# Monitor_strip.net
KiCad netlist of a schematic drawn in EAGLE
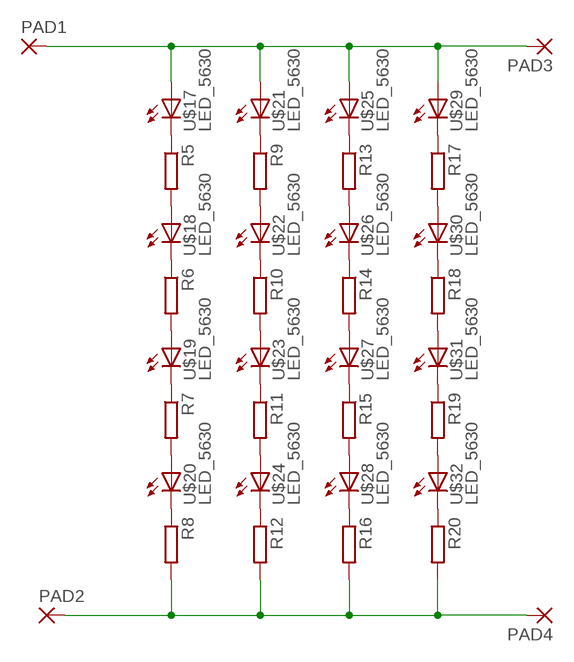
[diagram p0: schematic, sheet 1]

(export (version "E")
  (design (tool "Eeschema 10.0.6"))
  (components
    (comp (ref "PAD1")
      (value "SMD2")
      (footprint "eagle-import:SMD1,27-2,54")
      (libsource (lib "eagle-import") (part "SMD2"))
    )
    (comp (ref "PAD2")
      (value "SMD2")
      (footprint "eagle-import:SMD1,27-2,54")
      (libsource (lib "eagle-import") (part "SMD2"))
    )
    (comp (ref "PAD3")
      (value "SMD2")
      (footprint "eagle-import:SMD1,27-2,54")
      (libsource (lib "eagle-import") (part "SMD2"))
    )
    (comp (ref "PAD4")
      (value "SMD2")
      (footprint "eagle-import:SMD1,27-2,54")
      (libsource (lib "eagle-import") (part "SMD2"))
    )
    (comp (ref "R5")
      (value "R_0805")
      (footprint "eagle-import:R0805")
      (libsource (lib "eagle-import") (part "R_0805"))
    )
    (comp (ref "R6")
      (value "R_0805")
      (footprint "eagle-import:R0805")
      (libsource (lib "eagle-import") (part "R_0805"))
    )
    (comp (ref "R7")
      (value "R_0805")
      (footprint "eagle-import:R0805")
      (libsource (lib "eagle-import") (part "R_0805"))
    )
    (comp (ref "R8")
      (value "R_0805")
      (footprint "eagle-import:R0805")
      (libsource (lib "eagle-import") (part "R_0805"))
    )
    (comp (ref "R9")
      (value "R_0805")
      (footprint "eagle-import:R0805")
      (libsource (lib "eagle-import") (part "R_0805"))
    )
    (comp (ref "R10")
      (value "R_0805")
      (footprint "eagle-import:R0805")
      (libsource (lib "eagle-import") (part "R_0805"))
    )
    (comp (ref "R11")
      (value "R_0805")
      (footprint "eagle-import:R0805")
      (libsource (lib "eagle-import") (part "R_0805"))
    )
    (comp (ref "R12")
      (value "R_0805")
      (footprint "eagle-import:R0805")
      (libsource (lib "eagle-import") (part "R_0805"))
    )
    (comp (ref "R13")
      (value "R_0805")
      (footprint "eagle-import:R0805")
      (libsource (lib "eagle-import") (part "R_0805"))
    )
    (comp (ref "R14")
      (value "R_0805")
      (footprint "eagle-import:R0805")
      (libsource (lib "eagle-import") (part "R_0805"))
    )
    (comp (ref "R15")
      (value "R_0805")
      (footprint "eagle-import:R0805")
      (libsource (lib "eagle-import") (part "R_0805"))
    )
    (comp (ref "R16")
      (value "R_0805")
      (footprint "eagle-import:R0805")
      (libsource (lib "eagle-import") (part "R_0805"))
    )
    (comp (ref "R17")
      (value "R_0805")
      (footprint "eagle-import:R0805")
      (libsource (lib "eagle-import") (part "R_0805"))
    )
    (comp (ref "R18")
      (value "R_0805")
      (footprint "eagle-import:R0805")
      (libsource (lib "eagle-import") (part "R_0805"))
    )
    (comp (ref "R19")
      (value "R_0805")
      (footprint "eagle-import:R0805")
      (libsource (lib "eagle-import") (part "R_0805"))
    )
    (comp (ref "R20")
      (value "R_0805")
      (footprint "eagle-import:R0805")
      (libsource (lib "eagle-import") (part "R_0805"))
    )
    (comp (ref "U$17")
      (value "LED_5630")
      (footprint "eagle-import:LED5730")
      (libsource (lib "eagle-import") (part "LED_5630"))
    )
    (comp (ref "U$18")
      (value "LED_5630")
      (footprint "eagle-import:LED5730")
      (libsource (lib "eagle-import") (part "LED_5630"))
    )
    (comp (ref "U$19")
      (value "LED_5630")
      (footprint "eagle-import:LED5730")
      (libsource (lib "eagle-import") (part "LED_5630"))
    )
    (comp (ref "U$20")
      (value "LED_5630")
      (footprint "eagle-import:LED5730")
      (libsource (lib "eagle-import") (part "LED_5630"))
    )
    (comp (ref "U$21")
      (value "LED_5630")
      (footprint "eagle-import:LED5730")
      (libsource (lib "eagle-import") (part "LED_5630"))
    )
    (comp (ref "U$22")
      (value "LED_5630")
      (footprint "eagle-import:LED5730")
      (libsource (lib "eagle-import") (part "LED_5630"))
    )
    (comp (ref "U$23")
      (value "LED_5630")
      (footprint "eagle-import:LED5730")
      (libsource (lib "eagle-import") (part "LED_5630"))
    )
    (comp (ref "U$24")
      (value "LED_5630")
      (footprint "eagle-import:LED5730")
      (libsource (lib "eagle-import") (part "LED_5630"))
    )
    (comp (ref "U$25")
      (value "LED_5630")
      (footprint "eagle-import:LED5730")
      (libsource (lib "eagle-import") (part "LED_5630"))
    )
    (comp (ref "U$26")
      (value "LED_5630")
      (footprint "eagle-import:LED5730")
      (libsource (lib "eagle-import") (part "LED_5630"))
    )
    (comp (ref "U$27")
      (value "LED_5630")
      (footprint "eagle-import:LED5730")
      (libsource (lib "eagle-import") (part "LED_5630"))
    )
    (comp (ref "U$28")
      (value "LED_5630")
      (footprint "eagle-import:LED5730")
      (libsource (lib "eagle-import") (part "LED_5630"))
    )
    (comp (ref "U$29")
      (value "LED_5630")
      (footprint "eagle-import:LED5730")
      (libsource (lib "eagle-import") (part "LED_5630"))
    )
    (comp (ref "U$30")
      (value "LED_5630")
      (footprint "eagle-import:LED5730")
      (libsource (lib "eagle-import") (part "LED_5630"))
    )
    (comp (ref "U$31")
      (value "LED_5630")
      (footprint "eagle-import:LED5730")
      (libsource (lib "eagle-import") (part "LED_5630"))
    )
    (comp (ref "U$32")
      (value "LED_5630")
      (footprint "eagle-import:LED5730")
      (libsource (lib "eagle-import") (part "LED_5630"))
    )
  )
  (nets
    (net (code "1") (name "Net-(PAD1-P)") (class "Default")
      (node (ref "PAD1") (pin "1") (pinfunction "P_1") (pintype "passive"))
      (node (ref "PAD3") (pin "1") (pinfunction "P_1") (pintype "passive"))
      (node (ref "U$17") (pin "A") (pinfunction "A_A") (pintype "passive"))
      (node (ref "U$17") (pin "A1") (pinfunction "A_A1") (pintype "passive"))
      (node (ref "U$21") (pin "A") (pinfunction "A_A") (pintype "passive"))
      (node (ref "U$21") (pin "A1") (pinfunction "A_A1") (pintype "passive"))
      (node (ref "U$25") (pin "A") (pinfunction "A_A") (pintype "passive"))
      (node (ref "U$25") (pin "A1") (pinfunction "A_A1") (pintype "passive"))
      (node (ref "U$29") (pin "A") (pinfunction "A_A") (pintype "passive"))
      (node (ref "U$29") (pin "A1") (pinfunction "A_A1") (pintype "passive"))
    )
    (net (code "2") (name "Net-(PAD2-P)") (class "Default")
      (node (ref "PAD2") (pin "1") (pinfunction "P_1") (pintype "passive"))
      (node (ref "PAD4") (pin "1") (pinfunction "P_1") (pintype "passive"))
      (node (ref "R12") (pin "2") (pinfunction "2_2") (pintype "passive"))
      (node (ref "R16") (pin "2") (pinfunction "2_2") (pintype "passive"))
      (node (ref "R20") (pin "2") (pinfunction "2_2") (pintype "passive"))
      (node (ref "R8") (pin "2") (pinfunction "2_2") (pintype "passive"))
    )
    (net (code "3") (name "Net-(R5-Pad1)") (class "Default")
      (node (ref "R5") (pin "1") (pinfunction "1_1") (pintype "passive"))
      (node (ref "U$17") (pin "C") (pinfunction "C_C") (pintype "passive"))
    )
    (net (code "4") (name "Net-(R5-Pad2)") (class "Default")
      (node (ref "R5") (pin "2") (pinfunction "2_2") (pintype "passive"))
      (node (ref "U$18") (pin "A") (pinfunction "A_A") (pintype "passive"))
      (node (ref "U$18") (pin "A1") (pinfunction "A_A1") (pintype "passive"))
    )
    (net (code "5") (name "Net-(R6-Pad1)") (class "Default")
      (node (ref "R6") (pin "1") (pinfunction "1_1") (pintype "passive"))
      (node (ref "U$18") (pin "C") (pinfunction "C_C") (pintype "passive"))
    )
    (net (code "6") (name "Net-(R6-Pad2)") (class "Default")
      (node (ref "R6") (pin "2") (pinfunction "2_2") (pintype "passive"))
      (node (ref "U$19") (pin "A") (pinfunction "A_A") (pintype "passive"))
      (node (ref "U$19") (pin "A1") (pinfunction "A_A1") (pintype "passive"))
    )
    (net (code "7") (name "Net-(R7-Pad1)") (class "Default")
      (node (ref "R7") (pin "1") (pinfunction "1_1") (pintype "passive"))
      (node (ref "U$19") (pin "C") (pinfunction "C_C") (pintype "passive"))
    )
    (net (code "8") (name "Net-(R7-Pad2)") (class "Default")
      (node (ref "R7") (pin "2") (pinfunction "2_2") (pintype "passive"))
      (node (ref "U$20") (pin "A") (pinfunction "A_A") (pintype "passive"))
      (node (ref "U$20") (pin "A1") (pinfunction "A_A1") (pintype "passive"))
    )
    (net (code "9") (name "Net-(R8-Pad1)") (class "Default")
      (node (ref "R8") (pin "1") (pinfunction "1_1") (pintype "passive"))
      (node (ref "U$20") (pin "C") (pinfunction "C_C") (pintype "passive"))
    )
    (net (code "10") (name "Net-(R9-Pad1)") (class "Default")
      (node (ref "R9") (pin "1") (pinfunction "1_1") (pintype "passive"))
      (node (ref "U$21") (pin "C") (pinfunction "C_C") (pintype "passive"))
    )
    (net (code "11") (name "Net-(R9-Pad2)") (class "Default")
      (node (ref "R9") (pin "2") (pinfunction "2_2") (pintype "passive"))
      (node (ref "U$22") (pin "A") (pinfunction "A_A") (pintype "passive"))
      (node (ref "U$22") (pin "A1") (pinfunction "A_A1") (pintype "passive"))
    )
    (net (code "12") (name "Net-(R10-Pad1)") (class "Default")
      (node (ref "R10") (pin "1") (pinfunction "1_1") (pintype "passive"))
      (node (ref "U$22") (pin "C") (pinfunction "C_C") (pintype "passive"))
    )
    (net (code "13") (name "Net-(R10-Pad2)") (class "Default")
      (node (ref "R10") (pin "2") (pinfunction "2_2") (pintype "passive"))
      (node (ref "U$23") (pin "A") (pinfunction "A_A") (pintype "passive"))
      (node (ref "U$23") (pin "A1") (pinfunction "A_A1") (pintype "passive"))
    )
    (net (code "14") (name "Net-(R11-Pad1)") (class "Default")
      (node (ref "R11") (pin "1") (pinfunction "1_1") (pintype "passive"))
      (node (ref "U$23") (pin "C") (pinfunction "C_C") (pintype "passive"))
    )
    (net (code "15") (name "Net-(R11-Pad2)") (class "Default")
      (node (ref "R11") (pin "2") (pinfunction "2_2") (pintype "passive"))
      (node (ref "U$24") (pin "A") (pinfunction "A_A") (pintype "passive"))
      (node (ref "U$24") (pin "A1") (pinfunction "A_A1") (pintype "passive"))
    )
    (net (code "16") (name "Net-(R12-Pad1)") (class "Default")
      (node (ref "R12") (pin "1") (pinfunction "1_1") (pintype "passive"))
      (node (ref "U$24") (pin "C") (pinfunction "C_C") (pintype "passive"))
    )
    (net (code "17") (name "Net-(R13-Pad1)") (class "Default")
      (node (ref "R13") (pin "1") (pinfunction "1_1") (pintype "passive"))
      (node (ref "U$25") (pin "C") (pinfunction "C_C") (pintype "passive"))
    )
    (net (code "18") (name "Net-(R13-Pad2)") (class "Default")
      (node (ref "R13") (pin "2") (pinfunction "2_2") (pintype "passive"))
      (node (ref "U$26") (pin "A") (pinfunction "A_A") (pintype "passive"))
      (node (ref "U$26") (pin "A1") (pinfunction "A_A1") (pintype "passive"))
    )
    (net (code "19") (name "Net-(R14-Pad1)") (class "Default")
      (node (ref "R14") (pin "1") (pinfunction "1_1") (pintype "passive"))
      (node (ref "U$26") (pin "C") (pinfunction "C_C") (pintype "passive"))
    )
    (net (code "20") (name "Net-(R14-Pad2)") (class "Default")
      (node (ref "R14") (pin "2") (pinfunction "2_2") (pintype "passive"))
      (node (ref "U$27") (pin "A") (pinfunction "A_A") (pintype "passive"))
      (node (ref "U$27") (pin "A1") (pinfunction "A_A1") (pintype "passive"))
    )
    (net (code "21") (name "Net-(R15-Pad1)") (class "Default")
      (node (ref "R15") (pin "1") (pinfunction "1_1") (pintype "passive"))
      (node (ref "U$27") (pin "C") (pinfunction "C_C") (pintype "passive"))
    )
    (net (code "22") (name "Net-(R15-Pad2)") (class "Default")
      (node (ref "R15") (pin "2") (pinfunction "2_2") (pintype "passive"))
      (node (ref "U$28") (pin "A") (pinfunction "A_A") (pintype "passive"))
      (node (ref "U$28") (pin "A1") (pinfunction "A_A1") (pintype "passive"))
    )
    (net (code "23") (name "Net-(R16-Pad1)") (class "Default")
      (node (ref "R16") (pin "1") (pinfunction "1_1") (pintype "passive"))
      (node (ref "U$28") (pin "C") (pinfunction "C_C") (pintype "passive"))
    )
    (net (code "24") (name "Net-(R17-Pad1)") (class "Default")
      (node (ref "R17") (pin "1") (pinfunction "1_1") (pintype "passive"))
      (node (ref "U$29") (pin "C") (pinfunction "C_C") (pintype "passive"))
    )
    (net (code "25") (name "Net-(R17-Pad2)") (class "Default")
      (node (ref "R17") (pin "2") (pinfunction "2_2") (pintype "passive"))
      (node (ref "U$30") (pin "A") (pinfunction "A_A") (pintype "passive"))
      (node (ref "U$30") (pin "A1") (pinfunction "A_A1") (pintype "passive"))
    )
    (net (code "26") (name "Net-(R18-Pad1)") (class "Default")
      (node (ref "R18") (pin "1") (pinfunction "1_1") (pintype "passive"))
      (node (ref "U$30") (pin "C") (pinfunction "C_C") (pintype "passive"))
    )
    (net (code "27") (name "Net-(R18-Pad2)") (class "Default")
      (node (ref "R18") (pin "2") (pinfunction "2_2") (pintype "passive"))
      (node (ref "U$31") (pin "A") (pinfunction "A_A") (pintype "passive"))
      (node (ref "U$31") (pin "A1") (pinfunction "A_A1") (pintype "passive"))
    )
    (net (code "28") (name "Net-(R19-Pad1)") (class "Default")
      (node (ref "R19") (pin "1") (pinfunction "1_1") (pintype "passive"))
      (node (ref "U$31") (pin "C") (pinfunction "C_C") (pintype "passive"))
    )
    (net (code "29") (name "Net-(R19-Pad2)") (class "Default")
      (node (ref "R19") (pin "2") (pinfunction "2_2") (pintype "passive"))
      (node (ref "U$32") (pin "A") (pinfunction "A_A") (pintype "passive"))
      (node (ref "U$32") (pin "A1") (pinfunction "A_A1") (pintype "passive"))
    )
    (net (code "30") (name "Net-(R20-Pad1)") (class "Default")
      (node (ref "R20") (pin "1") (pinfunction "1_1") (pintype "passive"))
      (node (ref "U$32") (pin "C") (pinfunction "C_C") (pintype "passive"))
    )
  )
)
